# mericiObvod.net
KiCad netlist of a schematic drawn in EAGLE
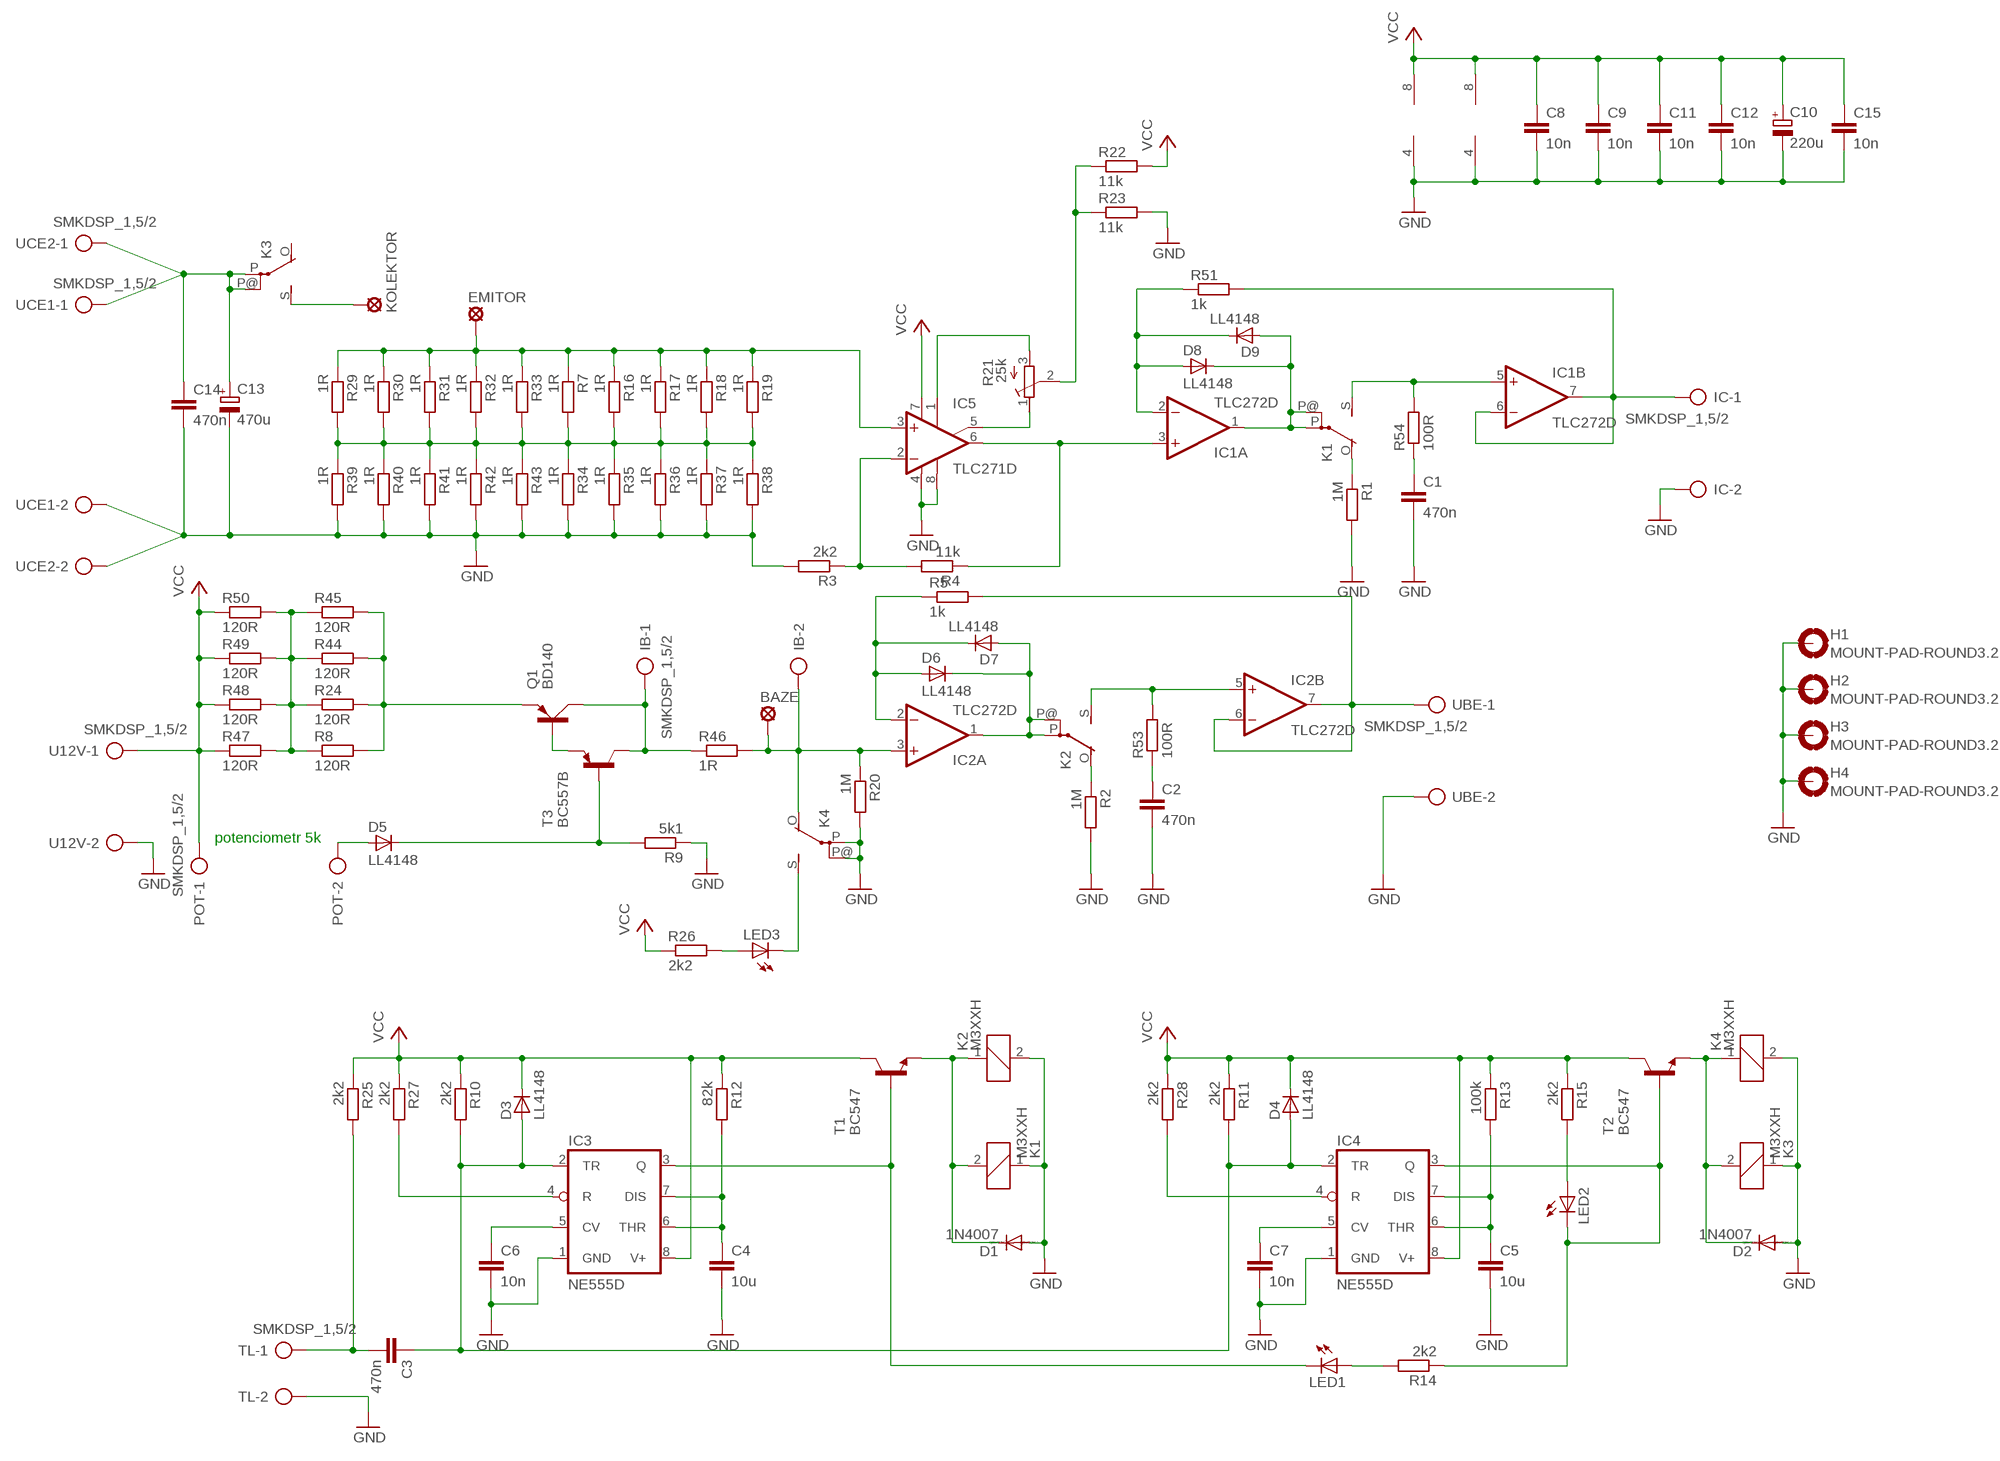
[diagram p0: schematic, sheet 1]

(export (version "E")
  (design (tool "Eeschema 10.0.6"))
  (components
    (comp (ref "BAZE")
      (value "SE13")
      (footprint "eagle-import:SE13")
      (libsource (lib "eagle-import") (part "SE13"))
    )
    (comp (ref "C1")
      (value "470n")
      (footprint "eagle-import:C0805K")
      (libsource (lib "eagle-import") (part "C-EUC0805K"))
    )
    (comp (ref "C2")
      (value "470n")
      (footprint "eagle-import:C0805K")
      (libsource (lib "eagle-import") (part "C-EUC0805K"))
    )
    (comp (ref "C3")
      (value "470n")
      (footprint "eagle-import:C0805K")
      (libsource (lib "eagle-import") (part "C-EUC0805K"))
    )
    (comp (ref "C4")
      (value "10u")
      (footprint "eagle-import:C0805K")
      (libsource (lib "eagle-import") (part "C-EUC0805K"))
    )
    (comp (ref "C5")
      (value "10u")
      (footprint "eagle-import:C0805K")
      (libsource (lib "eagle-import") (part "C-EUC0805K"))
    )
    (comp (ref "C6")
      (value "10n")
      (footprint "eagle-import:C0805K")
      (libsource (lib "eagle-import") (part "C-EUC0805K"))
    )
    (comp (ref "C7")
      (value "10n")
      (footprint "eagle-import:C0805K")
      (libsource (lib "eagle-import") (part "C-EUC0805K"))
    )
    (comp (ref "C8")
      (value "10n")
      (footprint "eagle-import:C0805K")
      (libsource (lib "eagle-import") (part "C-EUC0805K"))
    )
    (comp (ref "C9")
      (value "10n")
      (footprint "eagle-import:C0805K")
      (libsource (lib "eagle-import") (part "C-EUC0805K"))
    )
    (comp (ref "C10")
      (value "220u")
      (footprint "eagle-import:E5-8,5")
      (libsource (lib "eagle-import") (part "CPOL-EUE5-8.5"))
    )
    (comp (ref "C11")
      (value "10n")
      (footprint "eagle-import:C0805K")
      (libsource (lib "eagle-import") (part "C-EUC0805K"))
    )
    (comp (ref "C12")
      (value "10n")
      (footprint "eagle-import:C0805K")
      (libsource (lib "eagle-import") (part "C-EUC0805K"))
    )
    (comp (ref "C13")
      (value "470u")
      (footprint "eagle-import:E5-8,5")
      (libsource (lib "eagle-import") (part "CPOL-EUE5-8.5"))
    )
    (comp (ref "C14")
      (value "470n")
      (footprint "eagle-import:C050-030X075")
      (libsource (lib "eagle-import") (part "C-EU050-030X075"))
    )
    (comp (ref "C15")
      (value "10n")
      (footprint "eagle-import:C0805K")
      (libsource (lib "eagle-import") (part "C-EUC0805K"))
    )
    (comp (ref "D1")
      (value "1N4007")
      (footprint "eagle-import:DO41-10")
      (libsource (lib "eagle-import") (part "DIODE-DO41-10"))
    )
    (comp (ref "D2")
      (value "1N4007")
      (footprint "eagle-import:DO41-10")
      (libsource (lib "eagle-import") (part "DIODE-DO41-10"))
    )
    (comp (ref "D3")
      (value "LL4148")
      (footprint "eagle-import:SOD80")
      (libsource (lib "eagle-import") (part "D-SOD-80"))
    )
    (comp (ref "D4")
      (value "LL4148")
      (footprint "eagle-import:SOD80")
      (libsource (lib "eagle-import") (part "D-SOD-80"))
    )
    (comp (ref "D5")
      (value "LL4148")
      (footprint "eagle-import:SOD80")
      (libsource (lib "eagle-import") (part "D-SOD-80"))
    )
    (comp (ref "D6")
      (value "LL4148")
      (footprint "eagle-import:SOD80")
      (libsource (lib "eagle-import") (part "D-SOD-80"))
    )
    (comp (ref "D7")
      (value "LL4148")
      (footprint "eagle-import:SOD80")
      (libsource (lib "eagle-import") (part "D-SOD-80"))
    )
    (comp (ref "D8")
      (value "LL4148")
      (footprint "eagle-import:SOD80")
      (libsource (lib "eagle-import") (part "D-SOD-80"))
    )
    (comp (ref "D9")
      (value "LL4148")
      (footprint "eagle-import:SOD80")
      (libsource (lib "eagle-import") (part "D-SOD-80"))
    )
    (comp (ref "EMITOR")
      (value "SE13")
      (footprint "eagle-import:SE13")
      (libsource (lib "eagle-import") (part "SE13"))
    )
    (comp (ref "H1")
      (value "MOUNT-PAD-ROUND3.2")
      (footprint "eagle-import:3,2-PAD")
      (libsource (lib "eagle-import") (part "MOUNT-PAD-ROUND3.2"))
    )
    (comp (ref "H2")
      (value "MOUNT-PAD-ROUND3.2")
      (footprint "eagle-import:3,2-PAD")
      (libsource (lib "eagle-import") (part "MOUNT-PAD-ROUND3.2"))
    )
    (comp (ref "H3")
      (value "MOUNT-PAD-ROUND3.2")
      (footprint "eagle-import:3,2-PAD")
      (libsource (lib "eagle-import") (part "MOUNT-PAD-ROUND3.2"))
    )
    (comp (ref "H4")
      (value "MOUNT-PAD-ROUND3.2")
      (footprint "eagle-import:3,2-PAD")
      (libsource (lib "eagle-import") (part "MOUNT-PAD-ROUND3.2"))
    )
    (comp (ref "IB")
      (value "SMKDSP_1,5/2")
      (footprint "eagle-import:SMKDSP_1,5_2")
      (fields (field (name "MF") "FARNELL") (field (name "MPN") "1733570"))
      (libsource (lib "eagle-import") (part "SMKDSP_1,5/2"))
    )
    (comp (ref "IC")
      (value "SMKDSP_1,5/2")
      (footprint "eagle-import:SMKDSP_1,5_2")
      (fields (field (name "MF") "FARNELL") (field (name "MPN") "1733570"))
      (libsource (lib "eagle-import") (part "SMKDSP_1,5/2"))
    )
    (comp (ref "IC1")
      (value "TLC272D")
      (footprint "eagle-import:SO08")
      (libsource (lib "eagle-import") (part "TLC272D"))
    )
    (comp (ref "IC2")
      (value "TLC272D")
      (footprint "eagle-import:SO08")
      (libsource (lib "eagle-import") (part "TLC272D"))
    )
    (comp (ref "IC3")
      (value "NE555D")
      (footprint "eagle-import:SO08")
      (libsource (lib "eagle-import") (part "555DNE"))
    )
    (comp (ref "IC4")
      (value "NE555D")
      (footprint "eagle-import:SO08")
      (libsource (lib "eagle-import") (part "555DNE"))
    )
    (comp (ref "IC5")
      (value "TLC271D")
      (footprint "eagle-import:SO08")
      (libsource (lib "eagle-import") (part "TLC271D"))
    )
    (comp (ref "K1")
      (value "M3XXH")
      (footprint "eagle-import:M3XXH")
      (libsource (lib "eagle-import") (part "M3XXH"))
    )
    (comp (ref "K2")
      (value "M3XXH")
      (footprint "eagle-import:M3XXH")
      (libsource (lib "eagle-import") (part "M3XXH"))
    )
    (comp (ref "K3")
      (value "M3XXH")
      (footprint "eagle-import:M3XXH")
      (libsource (lib "eagle-import") (part "M3XXH"))
    )
    (comp (ref "K4")
      (value "M3XXH")
      (footprint "eagle-import:M3XXH")
      (libsource (lib "eagle-import") (part "M3XXH"))
    )
    (comp (ref "KOLEKTOR")
      (value "SE13")
      (footprint "eagle-import:SE13")
      (libsource (lib "eagle-import") (part "SE13"))
    )
    (comp (ref "LED1")
      (value "LED3MM")
      (footprint "eagle-import:LED3MM")
      (libsource (lib "eagle-import") (part "LED3MM"))
    )
    (comp (ref "LED2")
      (value "LED3MM")
      (footprint "eagle-import:LED3MM")
      (libsource (lib "eagle-import") (part "LED3MM"))
    )
    (comp (ref "LED3")
      (value "LED3MM")
      (footprint "eagle-import:LED3MM")
      (libsource (lib "eagle-import") (part "LED3MM"))
    )
    (comp (ref "POT")
      (value "SMKDSP_1,5/2")
      (footprint "eagle-import:SMKDSP_1,5_2")
      (fields (field (name "MF") "FARNELL") (field (name "MPN") "1733570"))
      (libsource (lib "eagle-import") (part "SMKDSP_1,5/2"))
    )
    (comp (ref "Q1")
      (value "BD140")
      (footprint "eagle-import:TO126AV")
      (libsource (lib "eagle-import") (part "BD140"))
    )
    (comp (ref "R1")
      (value "1M")
      (footprint "eagle-import:R0805")
      (libsource (lib "eagle-import") (part "R-EU_R0805"))
    )
    (comp (ref "R2")
      (value "1M")
      (footprint "eagle-import:R0805")
      (libsource (lib "eagle-import") (part "R-EU_R0805"))
    )
    (comp (ref "R3")
      (value "2k2")
      (footprint "eagle-import:R0805")
      (libsource (lib "eagle-import") (part "R-EU_R0805"))
    )
    (comp (ref "R4")
      (value "11k")
      (footprint "eagle-import:R0805")
      (libsource (lib "eagle-import") (part "R-EU_R0805"))
    )
    (comp (ref "R5")
      (value "1k")
      (footprint "eagle-import:R0805")
      (libsource (lib "eagle-import") (part "R-EU_R0805"))
    )
    (comp (ref "R7")
      (value "1R")
      (footprint "eagle-import:R0805")
      (libsource (lib "eagle-import") (part "R-EU_R0805"))
    )
    (comp (ref "R8")
      (value "120R")
      (footprint "eagle-import:R0805")
      (libsource (lib "eagle-import") (part "R-EU_R0805"))
    )
    (comp (ref "R9")
      (value "5k1")
      (footprint "eagle-import:R0805")
      (libsource (lib "eagle-import") (part "R-EU_R0805"))
    )
    (comp (ref "R10")
      (value "2k2")
      (footprint "eagle-import:R0805")
      (libsource (lib "eagle-import") (part "R-EU_R0805"))
    )
    (comp (ref "R11")
      (value "2k2")
      (footprint "eagle-import:R0805")
      (libsource (lib "eagle-import") (part "R-EU_R0805"))
    )
    (comp (ref "R12")
      (value "82k")
      (footprint "eagle-import:R0805")
      (libsource (lib "eagle-import") (part "R-EU_R0805"))
    )
    (comp (ref "R13")
      (value "100k")
      (footprint "eagle-import:R0805")
      (libsource (lib "eagle-import") (part "R-EU_R0805"))
    )
    (comp (ref "R14")
      (value "2k2")
      (footprint "eagle-import:R0805")
      (libsource (lib "eagle-import") (part "R-EU_R0805"))
    )
    (comp (ref "R15")
      (value "2k2")
      (footprint "eagle-import:R0805")
      (libsource (lib "eagle-import") (part "R-EU_R0805"))
    )
    (comp (ref "R16")
      (value "1R")
      (footprint "eagle-import:R0805")
      (libsource (lib "eagle-import") (part "R-EU_R0805"))
    )
    (comp (ref "R17")
      (value "1R")
      (footprint "eagle-import:R0805")
      (libsource (lib "eagle-import") (part "R-EU_R0805"))
    )
    (comp (ref "R18")
      (value "1R")
      (footprint "eagle-import:R0805")
      (libsource (lib "eagle-import") (part "R-EU_R0805"))
    )
    (comp (ref "R19")
      (value "1R")
      (footprint "eagle-import:R0805")
      (libsource (lib "eagle-import") (part "R-EU_R0805"))
    )
    (comp (ref "R20")
      (value "1M")
      (footprint "eagle-import:R0805")
      (libsource (lib "eagle-import") (part "R-EU_R0805"))
    )
    (comp (ref "R21")
      (value "25k")
      (footprint "eagle-import:RTRIMT18")
      (libsource (lib "eagle-import") (part "R-TRIMMT18"))
    )
    (comp (ref "R22")
      (value "11k")
      (footprint "eagle-import:R0805")
      (libsource (lib "eagle-import") (part "R-EU_R0805"))
    )
    (comp (ref "R23")
      (value "11k")
      (footprint "eagle-import:R0805")
      (libsource (lib "eagle-import") (part "R-EU_R0805"))
    )
    (comp (ref "R24")
      (value "120R")
      (footprint "eagle-import:R0805")
      (libsource (lib "eagle-import") (part "R-EU_R0805"))
    )
    (comp (ref "R25")
      (value "2k2")
      (footprint "eagle-import:R0805")
      (libsource (lib "eagle-import") (part "R-EU_R0805"))
    )
    (comp (ref "R26")
      (value "2k2")
      (footprint "eagle-import:R0805")
      (libsource (lib "eagle-import") (part "R-EU_R0805"))
    )
    (comp (ref "R27")
      (value "2k2")
      (footprint "eagle-import:R0805")
      (libsource (lib "eagle-import") (part "R-EU_R0805"))
    )
    (comp (ref "R28")
      (value "2k2")
      (footprint "eagle-import:R0805")
      (libsource (lib "eagle-import") (part "R-EU_R0805"))
    )
    (comp (ref "R29")
      (value "1R")
      (footprint "eagle-import:R0805")
      (libsource (lib "eagle-import") (part "R-EU_R0805"))
    )
    (comp (ref "R30")
      (value "1R")
      (footprint "eagle-import:R0805")
      (libsource (lib "eagle-import") (part "R-EU_R0805"))
    )
    (comp (ref "R31")
      (value "1R")
      (footprint "eagle-import:R0805")
      (libsource (lib "eagle-import") (part "R-EU_R0805"))
    )
    (comp (ref "R32")
      (value "1R")
      (footprint "eagle-import:R0805")
      (libsource (lib "eagle-import") (part "R-EU_R0805"))
    )
    (comp (ref "R33")
      (value "1R")
      (footprint "eagle-import:R0805")
      (libsource (lib "eagle-import") (part "R-EU_R0805"))
    )
    (comp (ref "R34")
      (value "1R")
      (footprint "eagle-import:R0805")
      (libsource (lib "eagle-import") (part "R-EU_R0805"))
    )
    (comp (ref "R35")
      (value "1R")
      (footprint "eagle-import:R0805")
      (libsource (lib "eagle-import") (part "R-EU_R0805"))
    )
    (comp (ref "R36")
      (value "1R")
      (footprint "eagle-import:R0805")
      (libsource (lib "eagle-import") (part "R-EU_R0805"))
    )
    (comp (ref "R37")
      (value "1R")
      (footprint "eagle-import:R0805")
      (libsource (lib "eagle-import") (part "R-EU_R0805"))
    )
    (comp (ref "R38")
      (value "1R")
      (footprint "eagle-import:R0805")
      (libsource (lib "eagle-import") (part "R-EU_R0805"))
    )
    (comp (ref "R39")
      (value "1R")
      (footprint "eagle-import:R0805")
      (libsource (lib "eagle-import") (part "R-EU_R0805"))
    )
    (comp (ref "R40")
      (value "1R")
      (footprint "eagle-import:R0805")
      (libsource (lib "eagle-import") (part "R-EU_R0805"))
    )
    (comp (ref "R41")
      (value "1R")
      (footprint "eagle-import:R0805")
      (libsource (lib "eagle-import") (part "R-EU_R0805"))
    )
    (comp (ref "R42")
      (value "1R")
      (footprint "eagle-import:R0805")
      (libsource (lib "eagle-import") (part "R-EU_R0805"))
    )
    (comp (ref "R43")
      (value "1R")
      (footprint "eagle-import:R0805")
      (libsource (lib "eagle-import") (part "R-EU_R0805"))
    )
    (comp (ref "R44")
      (value "120R")
      (footprint "eagle-import:R0805")
      (libsource (lib "eagle-import") (part "R-EU_R0805"))
    )
    (comp (ref "R45")
      (value "120R")
      (footprint "eagle-import:R0805")
      (libsource (lib "eagle-import") (part "R-EU_R0805"))
    )
    (comp (ref "R46")
      (value "1R")
      (footprint "eagle-import:R0805")
      (libsource (lib "eagle-import") (part "R-EU_R0805"))
    )
    (comp (ref "R47")
      (value "120R")
      (footprint "eagle-import:R0805")
      (libsource (lib "eagle-import") (part "R-EU_R0805"))
    )
    (comp (ref "R48")
      (value "120R")
      (footprint "eagle-import:R0805")
      (libsource (lib "eagle-import") (part "R-EU_R0805"))
    )
    (comp (ref "R49")
      (value "120R")
      (footprint "eagle-import:R0805")
      (libsource (lib "eagle-import") (part "R-EU_R0805"))
    )
    (comp (ref "R50")
      (value "120R")
      (footprint "eagle-import:R0805")
      (libsource (lib "eagle-import") (part "R-EU_R0805"))
    )
    (comp (ref "R51")
      (value "1k")
      (footprint "eagle-import:R0805")
      (libsource (lib "eagle-import") (part "R-EU_R0805"))
    )
    (comp (ref "R53")
      (value "100R")
      (footprint "eagle-import:R0805")
      (libsource (lib "eagle-import") (part "R-EU_R0805"))
    )
    (comp (ref "R54")
      (value "100R")
      (footprint "eagle-import:R0805")
      (libsource (lib "eagle-import") (part "R-EU_R0805"))
    )
    (comp (ref "T1")
      (value "BC547")
      (footprint "eagle-import:TO92-CBE")
      (libsource (lib "eagle-import") (part "-NPN-TO92-CBEBC547B"))
    )
    (comp (ref "T2")
      (value "BC547")
      (footprint "eagle-import:TO92-CBE")
      (libsource (lib "eagle-import") (part "-NPN-TO92-CBEBC547B"))
    )
    (comp (ref "T3")
      (value "BC557B")
      (footprint "eagle-import:TO92-EBC")
      (libsource (lib "eagle-import") (part "BC557B"))
    )
    (comp (ref "TL")
      (value "SMKDSP_1,5/2")
      (footprint "eagle-import:SMKDSP_1,5_2")
      (fields (field (name "MF") "FARNELL") (field (name "MPN") "1733570"))
      (libsource (lib "eagle-import") (part "SMKDSP_1,5/2"))
    )
    (comp (ref "U12V")
      (value "SMKDSP_1,5/2")
      (footprint "eagle-import:SMKDSP_1,5_2")
      (fields (field (name "MF") "FARNELL") (field (name "MPN") "1733570"))
      (libsource (lib "eagle-import") (part "SMKDSP_1,5/2"))
    )
    (comp (ref "UBE")
      (value "SMKDSP_1,5/2")
      (footprint "eagle-import:SMKDSP_1,5_2")
      (fields (field (name "MF") "FARNELL") (field (name "MPN") "1733570"))
      (libsource (lib "eagle-import") (part "SMKDSP_1,5/2"))
    )
    (comp (ref "UCE1")
      (value "SMKDSP_1,5/2")
      (footprint "eagle-import:SMKDSP_1,5_2")
      (fields (field (name "MF") "FARNELL") (field (name "MPN") "1733570"))
      (libsource (lib "eagle-import") (part "SMKDSP_1,5/2"))
    )
    (comp (ref "UCE2")
      (value "SMKDSP_1,5/2")
      (footprint "eagle-import:SMKDSP_1,5_2")
      (fields (field (name "MF") "FARNELL") (field (name "MPN") "1733570"))
      (libsource (lib "eagle-import") (part "SMKDSP_1,5/2"))
    )
  )
  (nets
    (net (code "1") (name "GND") (class "Default")
      (node (ref "C1") (pin "2") (pinfunction "2_2") (pintype "passive"))
      (node (ref "C10") (pin "-") (pinfunction "-_-") (pintype "passive"))
      (node (ref "C11") (pin "2") (pinfunction "2_2") (pintype "passive"))
      (node (ref "C12") (pin "2") (pinfunction "2_2") (pintype "passive"))
      (node (ref "C13") (pin "-") (pinfunction "-_-") (pintype "passive"))
      (node (ref "C14") (pin "2") (pinfunction "2_2") (pintype "passive"))
      (node (ref "C15") (pin "2") (pinfunction "2_2") (pintype "passive"))
      (node (ref "C2") (pin "2") (pinfunction "2_2") (pintype "passive"))
      (node (ref "C4") (pin "2") (pinfunction "2_2") (pintype "passive"))
      (node (ref "C5") (pin "2") (pinfunction "2_2") (pintype "passive"))
      (node (ref "C6") (pin "2") (pinfunction "2_2") (pintype "passive"))
      (node (ref "C7") (pin "2") (pinfunction "2_2") (pintype "passive"))
      (node (ref "C8") (pin "2") (pinfunction "2_2") (pintype "passive"))
      (node (ref "C9") (pin "2") (pinfunction "2_2") (pintype "passive"))
      (node (ref "D1") (pin "A") (pinfunction "A_A") (pintype "passive"))
      (node (ref "D2") (pin "A") (pinfunction "A_A") (pintype "passive"))
      (node (ref "H1") (pin "B3,2") (pinfunction "MOUNT_B3,2") (pintype "passive"))
      (node (ref "H2") (pin "B3,2") (pinfunction "MOUNT_B3,2") (pintype "passive"))
      (node (ref "H3") (pin "B3,2") (pinfunction "MOUNT_B3,2") (pintype "passive"))
      (node (ref "H4") (pin "B3,2") (pinfunction "MOUNT_B3,2") (pintype "passive"))
      (node (ref "IC") (pin "2") (pinfunction "KL_2") (pintype "passive"))
      (node (ref "IC1") (pin "4") (pinfunction "V-_4") (pintype "power_in"))
      (node (ref "IC2") (pin "4") (pinfunction "V-_4") (pintype "power_in"))
      (node (ref "IC3") (pin "1") (pinfunction "GND_1") (pintype "power_in"))
      (node (ref "IC4") (pin "1") (pinfunction "GND_1") (pintype "power_in"))
      (node (ref "IC5") (pin "4") (pinfunction "V-_4") (pintype "power_in"))
      (node (ref "IC5") (pin "8") (pinfunction "OPT_8") (pintype "passive"))
      (node (ref "K1") (pin "1") (pinfunction "1_1") (pintype "passive"))
      (node (ref "K2") (pin "2") (pinfunction "2_2") (pintype "passive"))
      (node (ref "K3") (pin "1") (pinfunction "1_1") (pintype "passive"))
      (node (ref "K4") (pin "2") (pinfunction "2_2") (pintype "passive"))
      (node (ref "K4") (pin "P") (pinfunction "P_P") (pintype "passive"))
      (node (ref "K4") (pin "P@") (pinfunction "P_P@") (pintype "passive"))
      (node (ref "R1") (pin "2") (pinfunction "2_2") (pintype "passive"))
      (node (ref "R2") (pin "2") (pinfunction "2_2") (pintype "passive"))
      (node (ref "R20") (pin "2") (pinfunction "2_2") (pintype "passive"))
      (node (ref "R23") (pin "2") (pinfunction "2_2") (pintype "passive"))
      (node (ref "R3") (pin "2") (pinfunction "2_2") (pintype "passive"))
      (node (ref "R34") (pin "2") (pinfunction "2_2") (pintype "passive"))
      (node (ref "R35") (pin "2") (pinfunction "2_2") (pintype "passive"))
      (node (ref "R36") (pin "2") (pinfunction "2_2") (pintype "passive"))
      (node (ref "R37") (pin "2") (pinfunction "2_2") (pintype "passive"))
      (node (ref "R38") (pin "2") (pinfunction "2_2") (pintype "passive"))
      (node (ref "R39") (pin "2") (pinfunction "2_2") (pintype "passive"))
      (node (ref "R40") (pin "2") (pinfunction "2_2") (pintype "passive"))
      (node (ref "R41") (pin "2") (pinfunction "2_2") (pintype "passive"))
      (node (ref "R42") (pin "2") (pinfunction "2_2") (pintype "passive"))
      (node (ref "R43") (pin "2") (pinfunction "2_2") (pintype "passive"))
      (node (ref "R9") (pin "1") (pinfunction "1_1") (pintype "passive"))
      (node (ref "TL") (pin "2") (pinfunction "KL_2") (pintype "passive"))
      (node (ref "U12V") (pin "2") (pinfunction "KL_2") (pintype "passive"))
      (node (ref "UBE") (pin "2") (pinfunction "KL_2") (pintype "passive"))
      (node (ref "UCE1") (pin "2") (pinfunction "KL_2") (pintype "passive"))
      (node (ref "UCE2") (pin "2") (pinfunction "KL_2") (pintype "passive"))
    )
    (net (code "2") (name "Net-(C1-Pad1)") (class "Default")
      (node (ref "C1") (pin "1") (pinfunction "1_1") (pintype "passive"))
      (node (ref "R54") (pin "1") (pinfunction "1_1") (pintype "passive"))
    )
    (net (code "3") (name "Net-(C2-Pad1)") (class "Default")
      (node (ref "C2") (pin "1") (pinfunction "1_1") (pintype "passive"))
      (node (ref "R53") (pin "1") (pinfunction "1_1") (pintype "passive"))
    )
    (net (code "4") (name "Net-(D1-PadC)") (class "Default")
      (node (ref "D1") (pin "C") (pinfunction "C_C") (pintype "passive"))
      (node (ref "K1") (pin "2") (pinfunction "2_2") (pintype "passive"))
      (node (ref "K2") (pin "1") (pinfunction "1_1") (pintype "passive"))
      (node (ref "T1") (pin "E") (pinfunction "E_E") (pintype "passive"))
    )
    (net (code "5") (name "Net-(D2-PadC)") (class "Default")
      (node (ref "D2") (pin "C") (pinfunction "C_C") (pintype "passive"))
      (node (ref "K3") (pin "2") (pinfunction "2_2") (pintype "passive"))
      (node (ref "K4") (pin "1") (pinfunction "1_1") (pintype "passive"))
      (node (ref "T2") (pin "E") (pinfunction "E_E") (pintype "passive"))
    )
    (net (code "6") (name "Net-(D3-A)") (class "Default")
      (node (ref "C3") (pin "1") (pinfunction "1_1") (pintype "passive"))
      (node (ref "D3") (pin "2") (pinfunction "A_2") (pintype "passive"))
      (node (ref "D4") (pin "2") (pinfunction "A_2") (pintype "passive"))
      (node (ref "IC3") (pin "2") (pinfunction "TR_2") (pintype "input"))
      (node (ref "IC4") (pin "2") (pinfunction "TR_2") (pintype "input"))
      (node (ref "R10") (pin "2") (pinfunction "2_2") (pintype "passive"))
      (node (ref "R11") (pin "2") (pinfunction "2_2") (pintype "passive"))
    )
    (net (code "7") (name "Net-(D5-A)") (class "Default")
      (node (ref "D5") (pin "2") (pinfunction "A_2") (pintype "passive"))
      (node (ref "POT") (pin "2") (pinfunction "KL_2") (pintype "passive"))
    )
    (net (code "8") (name "Net-(D5-C)") (class "Default")
      (node (ref "D5") (pin "1") (pinfunction "C_1") (pintype "passive"))
      (node (ref "R9") (pin "2") (pinfunction "2_2") (pintype "passive"))
      (node (ref "T3") (pin "B") (pinfunction "B_B") (pintype "passive"))
    )
    (net (code "9") (name "Net-(D6-A)") (class "Default")
      (node (ref "D6") (pin "2") (pinfunction "A_2") (pintype "passive"))
      (node (ref "D7") (pin "1") (pinfunction "C_1") (pintype "passive"))
      (node (ref "IC2") (pin "2") (pinfunction "-IN_2") (pintype "input"))
      (node (ref "R5") (pin "1") (pinfunction "1_1") (pintype "passive"))
    )
    (net (code "10") (name "Net-(D6-C)") (class "Default")
      (node (ref "D6") (pin "1") (pinfunction "C_1") (pintype "passive"))
      (node (ref "D7") (pin "2") (pinfunction "A_2") (pintype "passive"))
      (node (ref "IC2") (pin "1") (pinfunction "OUT_1") (pintype "output"))
      (node (ref "K2") (pin "P") (pinfunction "P_P") (pintype "passive"))
      (node (ref "K2") (pin "P@") (pinfunction "P_P@") (pintype "passive"))
    )
    (net (code "11") (name "Net-(D8-A)") (class "Default")
      (node (ref "D8") (pin "2") (pinfunction "A_2") (pintype "passive"))
      (node (ref "D9") (pin "1") (pinfunction "C_1") (pintype "passive"))
      (node (ref "IC1") (pin "2") (pinfunction "-IN_2") (pintype "input"))
      (node (ref "R51") (pin "1") (pinfunction "1_1") (pintype "passive"))
    )
    (net (code "12") (name "Net-(D8-C)") (class "Default")
      (node (ref "D8") (pin "1") (pinfunction "C_1") (pintype "passive"))
      (node (ref "D9") (pin "2") (pinfunction "A_2") (pintype "passive"))
      (node (ref "IC1") (pin "1") (pinfunction "OUT_1") (pintype "output"))
      (node (ref "K1") (pin "P") (pinfunction "P_P") (pintype "passive"))
      (node (ref "K1") (pin "P@") (pinfunction "P_P@") (pintype "passive"))
    )
    (net (code "13") (name "Net-(IBA-KL)") (class "Default")
      (node (ref "IB") (pin "1") (pinfunction "KL_1") (pintype "passive"))
      (node (ref "Q1") (pin "C") (pinfunction "C_C") (pintype "passive"))
      (node (ref "R46") (pin "1") (pinfunction "1_1") (pintype "passive"))
      (node (ref "T3") (pin "C") (pinfunction "C_C") (pintype "passive"))
    )
    (net (code "14") (name "Net-(IBB-KL)") (class "Default")
      (node (ref "BAZE") (pin "MP") (pinfunction "MP_MP") (pintype "passive"))
      (node (ref "IB") (pin "2") (pinfunction "KL_2") (pintype "passive"))
      (node (ref "IC2") (pin "3") (pinfunction "+IN_3") (pintype "input"))
      (node (ref "K4") (pin "O") (pinfunction "O_O") (pintype "passive"))
      (node (ref "R20") (pin "1") (pinfunction "1_1") (pintype "passive"))
      (node (ref "R46") (pin "2") (pinfunction "2_2") (pintype "passive"))
    )
    (net (code "15") (name "Net-(IC1A-+IN)") (class "Default")
      (node (ref "IC1") (pin "3") (pinfunction "+IN_3") (pintype "input"))
      (node (ref "IC5") (pin "6") (pinfunction "OUT_6") (pintype "output"))
      (node (ref "R4") (pin "1") (pinfunction "1_1") (pintype "passive"))
    )
    (net (code "16") (name "Net-(IC1B-+IN)") (class "Default")
      (node (ref "IC1") (pin "5") (pinfunction "+IN_5") (pintype "input"))
      (node (ref "K1") (pin "S") (pinfunction "S_S") (pintype "passive"))
      (node (ref "R54") (pin "2") (pinfunction "2_2") (pintype "passive"))
    )
    (net (code "17") (name "Net-(IC1B--IN)") (class "Default")
      (node (ref "IC") (pin "1") (pinfunction "KL_1") (pintype "passive"))
      (node (ref "IC1") (pin "6") (pinfunction "-IN_6") (pintype "input"))
      (node (ref "IC1") (pin "7") (pinfunction "OUT_7") (pintype "output"))
      (node (ref "R51") (pin "2") (pinfunction "2_2") (pintype "passive"))
    )
    (net (code "18") (name "Net-(IC2B-+IN)") (class "Default")
      (node (ref "IC2") (pin "5") (pinfunction "+IN_5") (pintype "input"))
      (node (ref "K2") (pin "S") (pinfunction "S_S") (pintype "passive"))
      (node (ref "R53") (pin "2") (pinfunction "2_2") (pintype "passive"))
    )
    (net (code "19") (name "Net-(IC2B--IN)") (class "Default")
      (node (ref "IC2") (pin "6") (pinfunction "-IN_6") (pintype "input"))
      (node (ref "IC2") (pin "7") (pinfunction "OUT_7") (pintype "output"))
      (node (ref "R5") (pin "2") (pinfunction "2_2") (pintype "passive"))
      (node (ref "UBE") (pin "1") (pinfunction "KL_1") (pintype "passive"))
    )
    (net (code "20") (name "Net-(IC3-CV)") (class "Default")
      (node (ref "C6") (pin "1") (pinfunction "1_1") (pintype "passive"))
      (node (ref "IC3") (pin "5") (pinfunction "CV_5") (pintype "input"))
    )
    (net (code "21") (name "Net-(IC3-DIS)") (class "Default")
      (node (ref "C4") (pin "1") (pinfunction "1_1") (pintype "passive"))
      (node (ref "IC3") (pin "6") (pinfunction "THR_6") (pintype "input"))
      (node (ref "IC3") (pin "7") (pinfunction "DIS_7") (pintype "input"))
      (node (ref "R12") (pin "2") (pinfunction "2_2") (pintype "passive"))
    )
    (net (code "22") (name "Net-(IC3-Q)") (class "Default")
      (node (ref "IC3") (pin "3") (pinfunction "Q_3") (pintype "output"))
      (node (ref "LED1") (pin "K") (pinfunction "C_K") (pintype "passive"))
      (node (ref "T1") (pin "B") (pinfunction "B_B") (pintype "passive"))
    )
    (net (code "23") (name "Net-(IC3-R)") (class "Default")
      (node (ref "IC3") (pin "4") (pinfunction "R_4") (pintype "input"))
      (node (ref "R27") (pin "2") (pinfunction "2_2") (pintype "passive"))
    )
    (net (code "24") (name "Net-(IC4-CV)") (class "Default")
      (node (ref "C7") (pin "1") (pinfunction "1_1") (pintype "passive"))
      (node (ref "IC4") (pin "5") (pinfunction "CV_5") (pintype "input"))
    )
    (net (code "25") (name "Net-(IC4-DIS)") (class "Default")
      (node (ref "C5") (pin "1") (pinfunction "1_1") (pintype "passive"))
      (node (ref "IC4") (pin "6") (pinfunction "THR_6") (pintype "input"))
      (node (ref "IC4") (pin "7") (pinfunction "DIS_7") (pintype "input"))
      (node (ref "R13") (pin "2") (pinfunction "2_2") (pintype "passive"))
    )
    (net (code "26") (name "Net-(IC4-Q)") (class "Default")
      (node (ref "IC4") (pin "3") (pinfunction "Q_3") (pintype "output"))
      (node (ref "LED2") (pin "K") (pinfunction "C_K") (pintype "passive"))
      (node (ref "R14") (pin "1") (pinfunction "1_1") (pintype "passive"))
      (node (ref "T2") (pin "B") (pinfunction "B_B") (pintype "passive"))
    )
    (net (code "27") (name "Net-(IC4-R)") (class "Default")
      (node (ref "IC4") (pin "4") (pinfunction "R_4") (pintype "input"))
      (node (ref "R28") (pin "2") (pinfunction "2_2") (pintype "passive"))
    )
    (net (code "28") (name "Net-(IC5-+IN)") (class "Default")
      (node (ref "EMITOR") (pin "MP") (pinfunction "MP_MP") (pintype "passive"))
      (node (ref "IC5") (pin "3") (pinfunction "+IN_3") (pintype "input"))
      (node (ref "R16") (pin "1") (pinfunction "1_1") (pintype "passive"))
      (node (ref "R17") (pin "1") (pinfunction "1_1") (pintype "passive"))
      (node (ref "R18") (pin "1") (pinfunction "1_1") (pintype "passive"))
      (node (ref "R19") (pin "1") (pinfunction "1_1") (pintype "passive"))
      (node (ref "R29") (pin "1") (pinfunction "1_1") (pintype "passive"))
      (node (ref "R30") (pin "1") (pinfunction "1_1") (pintype "passive"))
      (node (ref "R31") (pin "1") (pinfunction "1_1") (pintype "passive"))
      (node (ref "R32") (pin "1") (pinfunction "1_1") (pintype "passive"))
      (node (ref "R33") (pin "1") (pinfunction "1_1") (pintype "passive"))
      (node (ref "R7") (pin "1") (pinfunction "1_1") (pintype "passive"))
    )
    (net (code "29") (name "Net-(IC5--IN)") (class "Default")
      (node (ref "IC5") (pin "2") (pinfunction "-IN_2") (pintype "input"))
      (node (ref "R3") (pin "1") (pinfunction "1_1") (pintype "passive"))
      (node (ref "R4") (pin "2") (pinfunction "2_2") (pintype "passive"))
    )
    (net (code "30") (name "Net-(IC5-ON1)") (class "Default")
      (node (ref "IC5") (pin "1") (pinfunction "ON1_1") (pintype "passive"))
      (node (ref "R21") (pin "3") (pinfunction "A_3") (pintype "passive"))
    )
    (net (code "31") (name "Net-(IC5-ON2)") (class "Default")
      (node (ref "IC5") (pin "5") (pinfunction "ON2_5") (pintype "passive"))
      (node (ref "R21") (pin "1") (pinfunction "E_1") (pintype "passive"))
    )
    (net (code "32") (name "Net-(K1-PadO)") (class "Default")
      (node (ref "K1") (pin "O") (pinfunction "O_O") (pintype "passive"))
      (node (ref "R1") (pin "1") (pinfunction "1_1") (pintype "passive"))
    )
    (net (code "33") (name "Net-(K2-PadO)") (class "Default")
      (node (ref "K2") (pin "O") (pinfunction "O_O") (pintype "passive"))
      (node (ref "R2") (pin "1") (pinfunction "1_1") (pintype "passive"))
    )
    (net (code "34") (name "Net-(K3-PadS)") (class "Default")
      (node (ref "K3") (pin "S") (pinfunction "S_S") (pintype "passive"))
      (node (ref "KOLEKTOR") (pin "MP") (pinfunction "MP_MP") (pintype "passive"))
    )
    (net (code "35") (name "Net-(LED1-PadA)") (class "Default")
      (node (ref "LED1") (pin "A") (pinfunction "A_A") (pintype "passive"))
      (node (ref "R14") (pin "2") (pinfunction "2_2") (pintype "passive"))
    )
    (net (code "36") (name "Net-(LED2-PadA)") (class "Default")
      (node (ref "LED2") (pin "A") (pinfunction "A_A") (pintype "passive"))
      (node (ref "R15") (pin "2") (pinfunction "2_2") (pintype "passive"))
    )
    (net (code "37") (name "Net-(LED3-C)") (class "Default")
      (node (ref "K4") (pin "S") (pinfunction "S_S") (pintype "passive"))
      (node (ref "LED3") (pin "K") (pinfunction "C_K") (pintype "passive"))
    )
    (net (code "38") (name "Net-(LED3-PadA)") (class "Default")
      (node (ref "LED3") (pin "A") (pinfunction "A_A") (pintype "passive"))
      (node (ref "R26") (pin "2") (pinfunction "2_2") (pintype "passive"))
    )
    (net (code "39") (name "Net-(Q1-PadB)") (class "Default")
      (node (ref "Q1") (pin "B") (pinfunction "B_B") (pintype "passive"))
      (node (ref "T3") (pin "E") (pinfunction "E_E") (pintype "passive"))
    )
    (net (code "40") (name "Net-(Q1-PadE)") (class "Default")
      (node (ref "Q1") (pin "E") (pinfunction "E_E") (pintype "passive"))
      (node (ref "R24") (pin "2") (pinfunction "2_2") (pintype "passive"))
      (node (ref "R44") (pin "2") (pinfunction "2_2") (pintype "passive"))
      (node (ref "R45") (pin "2") (pinfunction "2_2") (pintype "passive"))
      (node (ref "R8") (pin "2") (pinfunction "2_2") (pintype "passive"))
    )
    (net (code "41") (name "Net-(R16-Pad2)") (class "Default")
      (node (ref "R16") (pin "2") (pinfunction "2_2") (pintype "passive"))
      (node (ref "R17") (pin "2") (pinfunction "2_2") (pintype "passive"))
      (node (ref "R18") (pin "2") (pinfunction "2_2") (pintype "passive"))
      (node (ref "R19") (pin "2") (pinfunction "2_2") (pintype "passive"))
      (node (ref "R29") (pin "2") (pinfunction "2_2") (pintype "passive"))
      (node (ref "R30") (pin "2") (pinfunction "2_2") (pintype "passive"))
      (node (ref "R31") (pin "2") (pinfunction "2_2") (pintype "passive"))
      (node (ref "R32") (pin "2") (pinfunction "2_2") (pintype "passive"))
      (node (ref "R33") (pin "2") (pinfunction "2_2") (pintype "passive"))
      (node (ref "R34") (pin "1") (pinfunction "1_1") (pintype "passive"))
      (node (ref "R35") (pin "1") (pinfunction "1_1") (pintype "passive"))
      (node (ref "R36") (pin "1") (pinfunction "1_1") (pintype "passive"))
      (node (ref "R37") (pin "1") (pinfunction "1_1") (pintype "passive"))
      (node (ref "R38") (pin "1") (pinfunction "1_1") (pintype "passive"))
      (node (ref "R39") (pin "1") (pinfunction "1_1") (pintype "passive"))
      (node (ref "R40") (pin "1") (pinfunction "1_1") (pintype "passive"))
      (node (ref "R41") (pin "1") (pinfunction "1_1") (pintype "passive"))
      (node (ref "R42") (pin "1") (pinfunction "1_1") (pintype "passive"))
      (node (ref "R43") (pin "1") (pinfunction "1_1") (pintype "passive"))
      (node (ref "R7") (pin "2") (pinfunction "2_2") (pintype "passive"))
    )
    (net (code "42") (name "Net-(R21-S)") (class "Default")
      (node (ref "R21") (pin "2") (pinfunction "S_2") (pintype "passive"))
      (node (ref "R22") (pin "1") (pinfunction "1_1") (pintype "passive"))
      (node (ref "R23") (pin "1") (pinfunction "1_1") (pintype "passive"))
    )
    (net (code "43") (name "Net-(R24-Pad1)") (class "Default")
      (node (ref "R24") (pin "1") (pinfunction "1_1") (pintype "passive"))
      (node (ref "R44") (pin "1") (pinfunction "1_1") (pintype "passive"))
      (node (ref "R45") (pin "1") (pinfunction "1_1") (pintype "passive"))
      (node (ref "R47") (pin "2") (pinfunction "2_2") (pintype "passive"))
      (node (ref "R48") (pin "2") (pinfunction "2_2") (pintype "passive"))
      (node (ref "R49") (pin "2") (pinfunction "2_2") (pintype "passive"))
      (node (ref "R50") (pin "2") (pinfunction "2_2") (pintype "passive"))
      (node (ref "R8") (pin "1") (pinfunction "1_1") (pintype "passive"))
    )
    (net (code "44") (name "Net-(TLA-KL)") (class "Default")
      (node (ref "C3") (pin "2") (pinfunction "2_2") (pintype "passive"))
      (node (ref "R25") (pin "2") (pinfunction "2_2") (pintype "passive"))
      (node (ref "TL") (pin "1") (pinfunction "KL_1") (pintype "passive"))
    )
    (net (code "45") (name "Net-(UCE1A-KL)") (class "Default")
      (node (ref "C13") (pin "+") (pinfunction "+_+") (pintype "passive"))
      (node (ref "C14") (pin "1") (pinfunction "1_1") (pintype "passive"))
      (node (ref "K3") (pin "P") (pinfunction "P_P") (pintype "passive"))
      (node (ref "K3") (pin "P@") (pinfunction "P_P@") (pintype "passive"))
      (node (ref "UCE1") (pin "1") (pinfunction "KL_1") (pintype "passive"))
      (node (ref "UCE2") (pin "1") (pinfunction "KL_1") (pintype "passive"))
    )
    (net (code "46") (name "VCC") (class "Default")
      (node (ref "C10") (pin "+") (pinfunction "+_+") (pintype "passive"))
      (node (ref "C11") (pin "1") (pinfunction "1_1") (pintype "passive"))
      (node (ref "C12") (pin "1") (pinfunction "1_1") (pintype "passive"))
      (node (ref "C15") (pin "1") (pinfunction "1_1") (pintype "passive"))
      (node (ref "C8") (pin "1") (pinfunction "1_1") (pintype "passive"))
      (node (ref "C9") (pin "1") (pinfunction "1_1") (pintype "passive"))
      (node (ref "D3") (pin "1") (pinfunction "C_1") (pintype "passive"))
      (node (ref "D4") (pin "1") (pinfunction "C_1") (pintype "passive"))
      (node (ref "IC1") (pin "8") (pinfunction "V+_8") (pintype "power_in"))
      (node (ref "IC2") (pin "8") (pinfunction "V+_8") (pintype "power_in"))
      (node (ref "IC3") (pin "8") (pinfunction "V+_8") (pintype "power_in"))
      (node (ref "IC4") (pin "8") (pinfunction "V+_8") (pintype "power_in"))
      (node (ref "IC5") (pin "7") (pinfunction "V+_7") (pintype "power_in"))
      (node (ref "POT") (pin "1") (pinfunction "KL_1") (pintype "passive"))
      (node (ref "R10") (pin "1") (pinfunction "1_1") (pintype "passive"))
      (node (ref "R11") (pin "1") (pinfunction "1_1") (pintype "passive"))
      (node (ref "R12") (pin "1") (pinfunction "1_1") (pintype "passive"))
      (node (ref "R13") (pin "1") (pinfunction "1_1") (pintype "passive"))
      (node (ref "R15") (pin "1") (pinfunction "1_1") (pintype "passive"))
      (node (ref "R22") (pin "2") (pinfunction "2_2") (pintype "passive"))
      (node (ref "R25") (pin "1") (pinfunction "1_1") (pintype "passive"))
      (node (ref "R26") (pin "1") (pinfunction "1_1") (pintype "passive"))
      (node (ref "R27") (pin "1") (pinfunction "1_1") (pintype "passive"))
      (node (ref "R28") (pin "1") (pinfunction "1_1") (pintype "passive"))
      (node (ref "R47") (pin "1") (pinfunction "1_1") (pintype "passive"))
      (node (ref "R48") (pin "1") (pinfunction "1_1") (pintype "passive"))
      (node (ref "R49") (pin "1") (pinfunction "1_1") (pintype "passive"))
      (node (ref "R50") (pin "1") (pinfunction "1_1") (pintype "passive"))
      (node (ref "T1") (pin "C") (pinfunction "C_C") (pintype "passive"))
      (node (ref "T2") (pin "C") (pinfunction "C_C") (pintype "passive"))
      (node (ref "U12V") (pin "1") (pinfunction "KL_1") (pintype "passive"))
    )
    (net (code "47") (name "unconnected-(K3-PadO)") (class "Default")
      (node (ref "K3") (pin "O") (pinfunction "O_O") (pintype "passive"))
    )
  )
)
